# pt2399_delay.net
KiCad netlist of a schematic drawn in EAGLE
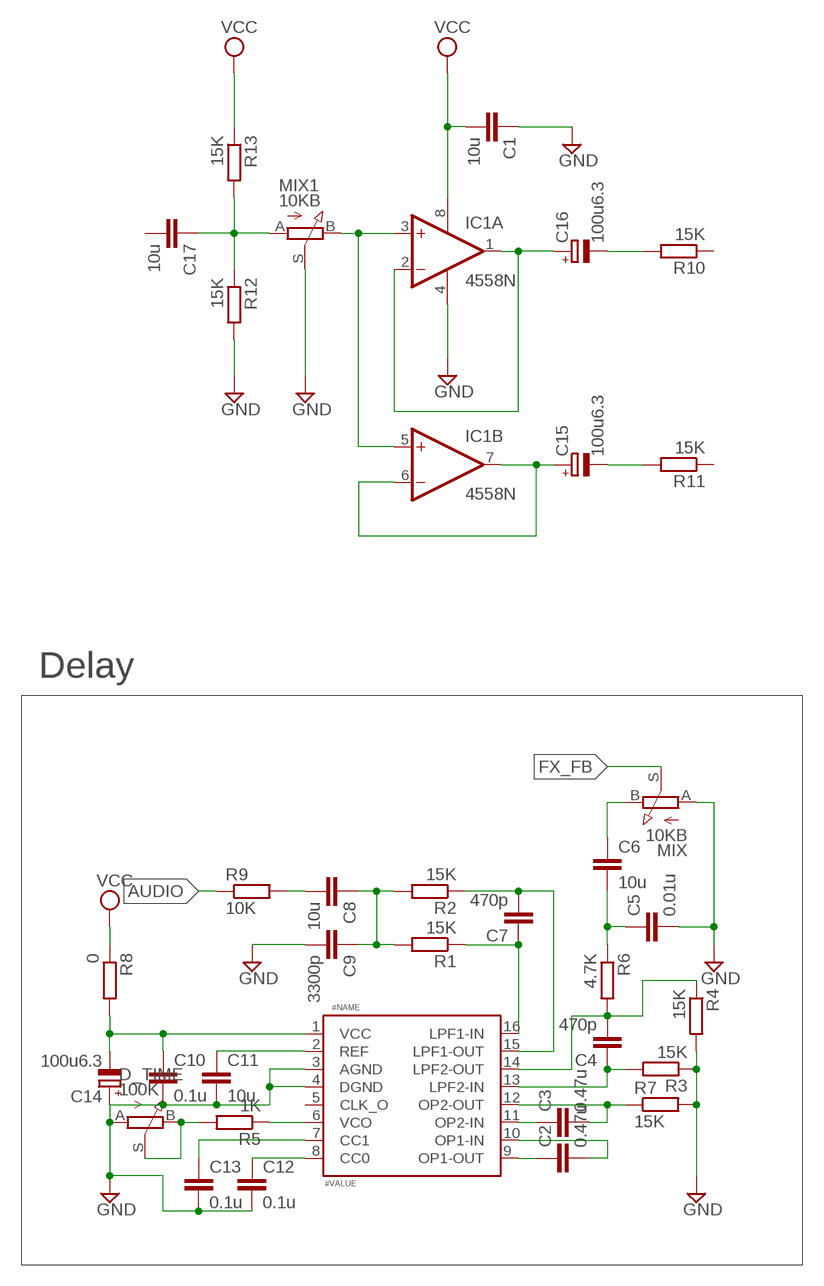
[diagram p0: schematic, sheet 1]

(export (version "E")
  (design (tool "Eeschema 10.0.6"))
  (components
    (comp (ref "C1")
      (value "10u")
      (footprint "eagle-import:C0805K")
      (libsource (lib "eagle-import") (part "C-EUC0805K"))
    )
    (comp (ref "C2")
      (value "0.47u")
      (footprint "eagle-import:C0805K")
      (libsource (lib "eagle-import") (part "C-EUC0805K"))
    )
    (comp (ref "C3")
      (value "0.47u")
      (footprint "eagle-import:C0805K")
      (libsource (lib "eagle-import") (part "C-EUC0805K"))
    )
    (comp (ref "C4")
      (value "470p")
      (footprint "eagle-import:C0805K")
      (libsource (lib "eagle-import") (part "C-EUC0805K"))
    )
    (comp (ref "C5")
      (value "0.01u")
      (footprint "eagle-import:C0805K")
      (libsource (lib "eagle-import") (part "C-EUC0805K"))
    )
    (comp (ref "C6")
      (value "10u")
      (footprint "eagle-import:C0805K")
      (libsource (lib "eagle-import") (part "C-EUC0805K"))
    )
    (comp (ref "C7")
      (value "470p")
      (footprint "eagle-import:C0805K")
      (libsource (lib "eagle-import") (part "C-EUC0805K"))
    )
    (comp (ref "C8")
      (value "10u")
      (footprint "eagle-import:C0805K")
      (libsource (lib "eagle-import") (part "C-EUC0805K"))
    )
    (comp (ref "C9")
      (value "3300p")
      (footprint "eagle-import:C0805K")
      (libsource (lib "eagle-import") (part "C-EUC0805K"))
    )
    (comp (ref "C10")
      (value "0.1u")
      (footprint "eagle-import:C0805K")
      (libsource (lib "eagle-import") (part "C-EUC0805K"))
    )
    (comp (ref "C11")
      (value "10u")
      (footprint "eagle-import:C0805K")
      (libsource (lib "eagle-import") (part "C-EUC0805K"))
    )
    (comp (ref "C12")
      (value "0.1u")
      (footprint "eagle-import:C0805K")
      (libsource (lib "eagle-import") (part "C-EUC0805K"))
    )
    (comp (ref "C13")
      (value "0.1u")
      (footprint "eagle-import:C0805K")
      (libsource (lib "eagle-import") (part "C-EUC0805K"))
    )
    (comp (ref "C14")
      (value "100u6.3")
      (footprint "eagle-import:TAP5-45")
      (libsource (lib "eagle-import") (part "CPOL-EUTAP5-45"))
    )
    (comp (ref "C15")
      (value "100u6.3")
      (footprint "eagle-import:TAP5-45")
      (libsource (lib "eagle-import") (part "CPOL-EUTAP5-45"))
    )
    (comp (ref "C16")
      (value "100u6.3")
      (footprint "eagle-import:TAP5-45")
      (libsource (lib "eagle-import") (part "CPOL-EUTAP5-45"))
    )
    (comp (ref "C17")
      (value "10u")
      (footprint "eagle-import:C0805K")
      (libsource (lib "eagle-import") (part "C-EUC0805K"))
    )
    (comp (ref "D_TIME")
      (value "100K")
      (footprint "eagle-import:RK09K113")
      (libsource (lib "eagle-import") (part "RK09K113"))
    )
    (comp (ref "IC1")
      (value "4558N")
      (footprint "eagle-import:DIP08")
      (libsource (lib "eagle-import") (part "4558N"))
    )
    (comp (ref "MIX")
      (value "10KB")
      (footprint "eagle-import:RK09K113")
      (libsource (lib "eagle-import") (part "RK09K113"))
    )
    (comp (ref "MIX1")
      (value "10KB")
      (footprint "eagle-import:RK09K113")
      (libsource (lib "eagle-import") (part "RK09K113"))
    )
    (comp (ref "R1")
      (value "15K")
      (footprint "eagle-import:2012_0805(1_8)")
      (libsource (lib "eagle-import") (part "RESISTOR2012/0805"))
    )
    (comp (ref "R2")
      (value "15K")
      (footprint "eagle-import:2012_0805(1_8)")
      (libsource (lib "eagle-import") (part "RESISTOR2012/0805"))
    )
    (comp (ref "R3")
      (value "15K")
      (footprint "eagle-import:2012_0805(1_8)")
      (libsource (lib "eagle-import") (part "RESISTOR2012/0805"))
    )
    (comp (ref "R4")
      (value "15K")
      (footprint "eagle-import:2012_0805(1_8)")
      (libsource (lib "eagle-import") (part "RESISTOR2012/0805"))
    )
    (comp (ref "R5")
      (value "1K")
      (footprint "eagle-import:2012_0805(1_8)")
      (libsource (lib "eagle-import") (part "RESISTOR2012/0805"))
    )
    (comp (ref "R6")
      (value "4.7K")
      (footprint "eagle-import:2012_0805(1_8)")
      (libsource (lib "eagle-import") (part "RESISTOR2012/0805"))
    )
    (comp (ref "R7")
      (value "15K")
      (footprint "eagle-import:2012_0805(1_8)")
      (libsource (lib "eagle-import") (part "RESISTOR2012/0805"))
    )
    (comp (ref "R8")
      (value "0")
      (footprint "eagle-import:2012_0805(1_8)")
      (libsource (lib "eagle-import") (part "RESISTOR2012/0805"))
    )
    (comp (ref "R9")
      (value "10K")
      (footprint "eagle-import:2012_0805(1_8)")
      (libsource (lib "eagle-import") (part "RESISTOR2012/0805"))
    )
    (comp (ref "R10")
      (value "15K")
      (footprint "eagle-import:2012_0805(1_8)")
      (libsource (lib "eagle-import") (part "RESISTOR2012/0805"))
    )
    (comp (ref "R11")
      (value "15K")
      (footprint "eagle-import:2012_0805(1_8)")
      (libsource (lib "eagle-import") (part "RESISTOR2012/0805"))
    )
    (comp (ref "R12")
      (value "15K")
      (footprint "eagle-import:2012_0805(1_8)")
      (libsource (lib "eagle-import") (part "RESISTOR2012/0805"))
    )
    (comp (ref "R13")
      (value "15K")
      (footprint "eagle-import:2012_0805(1_8)")
      (libsource (lib "eagle-import") (part "RESISTOR2012/0805"))
    )
    (comp (ref "U1")
      (value "PT2399")
      (footprint "eagle-import:DIL16")
      (libsource (lib "eagle-import") (part "PT2399"))
    )
  )
  (nets
    (net (code "1") (name "AUDIO") (class "Default")
      (node (ref "R9") (pin "1") (pinfunction "1_1") (pintype "passive"))
    )
    (net (code "2") (name "FX_FB") (class "Default")
      (node (ref "MIX") (pin "S") (pinfunction "S_S") (pintype "passive"))
    )
    (net (code "3") (name "GND") (class "Default")
      (node (ref "C1") (pin "1") (pinfunction "1_1") (pintype "passive"))
      (node (ref "C10") (pin "2") (pinfunction "2_2") (pintype "passive"))
      (node (ref "C11") (pin "2") (pinfunction "2_2") (pintype "passive"))
      (node (ref "C12") (pin "2") (pinfunction "2_2") (pintype "passive"))
      (node (ref "C13") (pin "2") (pinfunction "2_2") (pintype "passive"))
      (node (ref "C14") (pin "+") (pinfunction "+_+") (pintype "passive"))
      (node (ref "C5") (pin "2") (pinfunction "2_2") (pintype "passive"))
      (node (ref "C9") (pin "2") (pinfunction "2_2") (pintype "passive"))
      (node (ref "D_TIME") (pin "A") (pinfunction "A_A") (pintype "passive"))
      (node (ref "IC1") (pin "4") (pinfunction "V-_4") (pintype "power_in"))
      (node (ref "MIX") (pin "A") (pinfunction "A_A") (pintype "passive"))
      (node (ref "MIX1") (pin "S") (pinfunction "S_S") (pintype "passive"))
      (node (ref "R12") (pin "2") (pinfunction "2_2") (pintype "passive"))
      (node (ref "R3") (pin "1") (pinfunction "1_1") (pintype "passive"))
      (node (ref "R4") (pin "2") (pinfunction "2_2") (pintype "passive"))
      (node (ref "R7") (pin "2") (pinfunction "2_2") (pintype "passive"))
      (node (ref "U1") (pin "3") (pinfunction "AGND_3") (pintype "bidirectional"))
      (node (ref "U1") (pin "4") (pinfunction "DGND_4") (pintype "bidirectional"))
    )
    (net (code "4") (name "Net-(C5-Pad1)") (class "Default")
      (node (ref "C5") (pin "1") (pinfunction "1_1") (pintype "passive"))
      (node (ref "C6") (pin "2") (pinfunction "2_2") (pintype "passive"))
      (node (ref "R6") (pin "1") (pinfunction "1_1") (pintype "passive"))
    )
    (net (code "5") (name "Net-(C8-Pad1)") (class "Default")
      (node (ref "C8") (pin "1") (pinfunction "1_1") (pintype "passive"))
      (node (ref "C9") (pin "1") (pinfunction "1_1") (pintype "passive"))
      (node (ref "R1") (pin "2") (pinfunction "2_2") (pintype "passive"))
      (node (ref "R2") (pin "2") (pinfunction "2_2") (pintype "passive"))
    )
    (net (code "6") (name "Net-(C8-Pad2)") (class "Default")
      (node (ref "C8") (pin "2") (pinfunction "2_2") (pintype "passive"))
      (node (ref "R9") (pin "2") (pinfunction "2_2") (pintype "passive"))
    )
    (net (code "7") (name "Net-(C15-Pad-)") (class "Default")
      (node (ref "C15") (pin "-") (pinfunction "-_-") (pintype "passive"))
      (node (ref "R11") (pin "2") (pinfunction "2_2") (pintype "passive"))
    )
    (net (code "8") (name "Net-(C16-Pad-)") (class "Default")
      (node (ref "C16") (pin "-") (pinfunction "-_-") (pintype "passive"))
      (node (ref "R10") (pin "2") (pinfunction "2_2") (pintype "passive"))
    )
    (net (code "9") (name "Net-(C17-Pad1)") (class "Default")
      (node (ref "C17") (pin "1") (pinfunction "1_1") (pintype "passive"))
      (node (ref "MIX1") (pin "A") (pinfunction "A_A") (pintype "passive"))
      (node (ref "R12") (pin "1") (pinfunction "1_1") (pintype "passive"))
      (node (ref "R13") (pin "2") (pinfunction "2_2") (pintype "passive"))
    )
    (net (code "10") (name "Net-(D_TIME-E)") (class "Default")
      (node (ref "D_TIME") (pin "B") (pinfunction "E_B") (pintype "passive"))
      (node (ref "D_TIME") (pin "S") (pinfunction "S_S") (pintype "passive"))
      (node (ref "R5") (pin "2") (pinfunction "2_2") (pintype "passive"))
    )
    (net (code "11") (name "Net-(IC1A-+IN)") (class "Default")
      (node (ref "IC1") (pin "3") (pinfunction "+IN_3") (pintype "input"))
      (node (ref "IC1") (pin "5") (pinfunction "+IN_5") (pintype "input"))
      (node (ref "MIX1") (pin "B") (pinfunction "E_B") (pintype "passive"))
    )
    (net (code "12") (name "Net-(IC1A--IN)") (class "Default")
      (node (ref "C16") (pin "+") (pinfunction "+_+") (pintype "passive"))
      (node (ref "IC1") (pin "1") (pinfunction "OUT_1") (pintype "output"))
      (node (ref "IC1") (pin "2") (pinfunction "-IN_2") (pintype "input"))
    )
    (net (code "13") (name "Net-(IC1B--IN)") (class "Default")
      (node (ref "C15") (pin "+") (pinfunction "+_+") (pintype "passive"))
      (node (ref "IC1") (pin "6") (pinfunction "-IN_6") (pintype "input"))
      (node (ref "IC1") (pin "7") (pinfunction "OUT_7") (pintype "output"))
    )
    (net (code "14") (name "Net-(MIX-E)") (class "Default")
      (node (ref "C6") (pin "1") (pinfunction "1_1") (pintype "passive"))
      (node (ref "MIX") (pin "B") (pinfunction "E_B") (pintype "passive"))
    )
    (net (code "15") (name "Net-(U1-CC0)") (class "Default")
      (node (ref "C12") (pin "1") (pinfunction "1_1") (pintype "passive"))
      (node (ref "U1") (pin "8") (pinfunction "CC0_8") (pintype "bidirectional"))
    )
    (net (code "16") (name "Net-(U1-CC1)") (class "Default")
      (node (ref "C13") (pin "1") (pinfunction "1_1") (pintype "passive"))
      (node (ref "U1") (pin "7") (pinfunction "CC1_7") (pintype "bidirectional"))
    )
    (net (code "17") (name "Net-(U1-LPF1-IN)") (class "Default")
      (node (ref "C7") (pin "1") (pinfunction "1_1") (pintype "passive"))
      (node (ref "R1") (pin "1") (pinfunction "1_1") (pintype "passive"))
      (node (ref "U1") (pin "16") (pinfunction "LPF1-IN_16") (pintype "bidirectional"))
    )
    (net (code "18") (name "Net-(U1-LPF1-OUT)") (class "Default")
      (node (ref "C7") (pin "2") (pinfunction "2_2") (pintype "passive"))
      (node (ref "R2") (pin "1") (pinfunction "1_1") (pintype "passive"))
      (node (ref "U1") (pin "15") (pinfunction "LPF1-OUT_15") (pintype "bidirectional"))
    )
    (net (code "19") (name "Net-(U1-LPF2-IN)") (class "Default")
      (node (ref "C4") (pin "1") (pinfunction "1_1") (pintype "passive"))
      (node (ref "R3") (pin "2") (pinfunction "2_2") (pintype "passive"))
      (node (ref "U1") (pin "13") (pinfunction "LPF2-IN_13") (pintype "bidirectional"))
    )
    (net (code "20") (name "Net-(U1-LPF2-OUT)") (class "Default")
      (node (ref "C4") (pin "2") (pinfunction "2_2") (pintype "passive"))
      (node (ref "R4") (pin "1") (pinfunction "1_1") (pintype "passive"))
      (node (ref "R6") (pin "2") (pinfunction "2_2") (pintype "passive"))
      (node (ref "U1") (pin "14") (pinfunction "LPF2-OUT_14") (pintype "bidirectional"))
    )
    (net (code "21") (name "Net-(U1-OP1-IN)") (class "Default")
      (node (ref "C2") (pin "2") (pinfunction "2_2") (pintype "passive"))
      (node (ref "U1") (pin "10") (pinfunction "OP1-IN_10") (pintype "bidirectional"))
    )
    (net (code "22") (name "Net-(U1-OP1-OUT)") (class "Default")
      (node (ref "C2") (pin "1") (pinfunction "1_1") (pintype "passive"))
      (node (ref "U1") (pin "9") (pinfunction "OP1-OUT_9") (pintype "bidirectional"))
    )
    (net (code "23") (name "Net-(U1-OP2-IN)") (class "Default")
      (node (ref "C3") (pin "1") (pinfunction "1_1") (pintype "passive"))
      (node (ref "U1") (pin "11") (pinfunction "OP2-IN_11") (pintype "bidirectional"))
    )
    (net (code "24") (name "Net-(U1-OP2-OUT)") (class "Default")
      (node (ref "C3") (pin "2") (pinfunction "2_2") (pintype "passive"))
      (node (ref "R7") (pin "1") (pinfunction "1_1") (pintype "passive"))
      (node (ref "U1") (pin "12") (pinfunction "OP2-OUT_12") (pintype "bidirectional"))
    )
    (net (code "25") (name "Net-(U1-REF)") (class "Default")
      (node (ref "C11") (pin "1") (pinfunction "1_1") (pintype "passive"))
      (node (ref "U1") (pin "2") (pinfunction "REF_2") (pintype "bidirectional"))
    )
    (net (code "26") (name "Net-(U1-VCC)") (class "Default")
      (node (ref "C10") (pin "1") (pinfunction "1_1") (pintype "passive"))
      (node (ref "C14") (pin "-") (pinfunction "-_-") (pintype "passive"))
      (node (ref "R8") (pin "2") (pinfunction "2_2") (pintype "passive"))
      (node (ref "U1") (pin "1") (pinfunction "VCC_1") (pintype "bidirectional"))
    )
    (net (code "27") (name "Net-(U1-VCO)") (class "Default")
      (node (ref "R5") (pin "1") (pinfunction "1_1") (pintype "passive"))
      (node (ref "U1") (pin "6") (pinfunction "VCO_6") (pintype "bidirectional"))
    )
    (net (code "28") (name "VCC") (class "Default")
      (node (ref "C1") (pin "2") (pinfunction "2_2") (pintype "passive"))
      (node (ref "IC1") (pin "8") (pinfunction "V+_8") (pintype "power_in"))
      (node (ref "R13") (pin "1") (pinfunction "1_1") (pintype "passive"))
      (node (ref "R8") (pin "1") (pinfunction "1_1") (pintype "passive"))
    )
    (net (code "29") (name "unconnected-(C17-Pad2)") (class "Default")
      (node (ref "C17") (pin "2") (pinfunction "2_2") (pintype "passive"))
    )
    (net (code "30") (name "unconnected-(R10-Pad1)") (class "Default")
      (node (ref "R10") (pin "1") (pinfunction "1_1") (pintype "passive"))
    )
    (net (code "31") (name "unconnected-(R11-Pad1)") (class "Default")
      (node (ref "R11") (pin "1") (pinfunction "1_1") (pintype "passive"))
    )
    (net (code "32") (name "unconnected-(U1-CLK_O-Pad5)") (class "Default")
      (node (ref "U1") (pin "5") (pinfunction "CLK_O_5") (pintype "bidirectional"))
    )
  )
)
